# tuch-tara3.net
KiCad netlist of a schematic drawn in Altium Designer
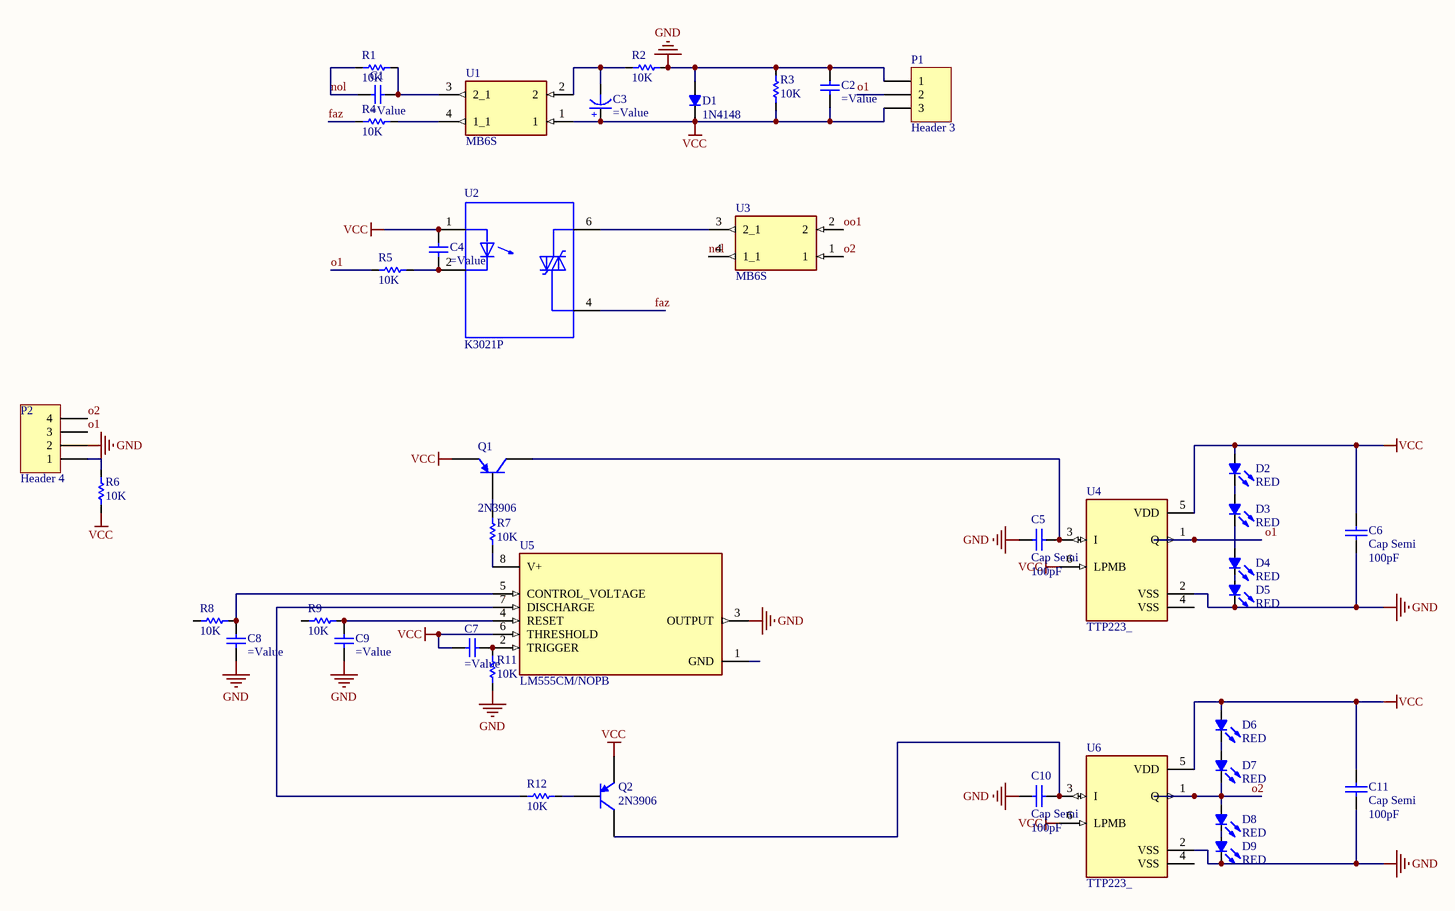
[diagram p0: tuch-tara3.SchDoc]

(export (version "E")
  (design (tool "Eeschema 10.0.6"))
  (components
    (comp (ref "C1")
      (value "~")
      (footprint "CAP-30")
      (description "Capacitor")
      (libsource (lib "AltiumLib1") (part "Capacitor"))
    )
    (comp (ref "C2")
      (value "~")
      (footprint "CAP 1206")
      (description "Capacitor")
      (libsource (lib "AltiumLib1") (part "Capacitor"))
    )
    (comp (ref "C3")
      (value "~")
      (footprint "ELEC-CAP-RAD10-20")
      (description "Electrolytic Capacitor")
      (libsource (lib "AltiumLib1") (part "Capacitor Electrolytic"))
    )
    (comp (ref "C4")
      (value "~")
      (footprint "CAP 1206")
      (description "Capacitor")
      (libsource (lib "AltiumLib1") (part "Capacitor"))
    )
    (comp (ref "C5")
      (value "Cap Semi")
      (footprint "AltiumLib1:CAP 0805")
      (description "Capacitor (Semiconductor SIM Model)")
      (fields (field (name "ALTIUM_VALUE") "100pF") (field (name "PUBLISHER") "Altium Limited"))
      (libsource (lib "Miscellaneous Devices") (part "Cap Semi"))
    )
    (comp (ref "C6")
      (value "Cap Semi")
      (footprint "C1206")
      (description "Capacitor (Semiconductor SIM Model)")
      (fields (field (name "ALTIUM_VALUE") "100pF") (field (name "PUBLISHER") "Altium Limited"))
      (libsource (lib "Miscellaneous Devices") (part "Cap Semi"))
    )
    (comp (ref "C7")
      (value "~")
      (footprint "CAP 0805")
      (description "Capacitor")
      (libsource (lib "AltiumLib1") (part "Capacitor"))
    )
    (comp (ref "C8")
      (value "~")
      (footprint "CAP 0805")
      (description "Capacitor")
      (libsource (lib "AltiumLib1") (part "Capacitor"))
    )
    (comp (ref "C9")
      (value "~")
      (footprint "CAP 0805")
      (description "Capacitor")
      (libsource (lib "AltiumLib1") (part "Capacitor"))
    )
    (comp (ref "C10")
      (value "Cap Semi")
      (footprint "AltiumLib1:CAP 0805")
      (description "Capacitor (Semiconductor SIM Model)")
      (fields (field (name "ALTIUM_VALUE") "100pF") (field (name "PUBLISHER") "Altium Limited"))
      (libsource (lib "Miscellaneous Devices") (part "Cap Semi"))
    )
    (comp (ref "C11")
      (value "Cap Semi")
      (footprint "C1206")
      (description "Capacitor (Semiconductor SIM Model)")
      (fields (field (name "ALTIUM_VALUE") "100pF") (field (name "PUBLISHER") "Altium Limited"))
      (libsource (lib "Miscellaneous Devices") (part "Cap Semi"))
    )
    (comp (ref "D1")
      (value "MODEL")
      (footprint "DO-41")
      (description "Diode")
      (fields (field (name "MODEL") "1N4148"))
      (libsource (lib "AltiumLib1") (part "Diode"))
    )
    (comp (ref "D2")
      (value "MODEL")
      (footprint "RES 1206 (3216X08L)")
      (description "Typical LED")
      (fields (field (name "COLOR") "RED"))
      (libsource (lib "AltiumLib1") (part "LED 5mm"))
    )
    (comp (ref "D3")
      (value "MODEL")
      (footprint "RES 1206 (3216X08L)")
      (description "Typical LED")
      (fields (field (name "COLOR") "RED"))
      (libsource (lib "AltiumLib1") (part "LED 5mm"))
    )
    (comp (ref "D4")
      (value "MODEL")
      (footprint "RES 1206 (3216X08L)")
      (description "Typical LED")
      (fields (field (name "COLOR") "RED"))
      (libsource (lib "AltiumLib1") (part "LED 5mm"))
    )
    (comp (ref "D5")
      (value "MODEL")
      (footprint "RES 1206 (3216X08L)")
      (description "Typical LED")
      (fields (field (name "COLOR") "RED"))
      (libsource (lib "AltiumLib1") (part "LED 5mm"))
    )
    (comp (ref "D6")
      (value "MODEL")
      (footprint "RES 1206 (3216X08L)")
      (description "Typical LED")
      (fields (field (name "COLOR") "RED"))
      (libsource (lib "AltiumLib1") (part "LED 5mm"))
    )
    (comp (ref "D7")
      (value "MODEL")
      (footprint "RES 1206 (3216X08L)")
      (description "Typical LED")
      (fields (field (name "COLOR") "RED"))
      (libsource (lib "AltiumLib1") (part "LED 5mm"))
    )
    (comp (ref "D8")
      (value "MODEL")
      (footprint "RES 1206 (3216X08L)")
      (description "Typical LED")
      (fields (field (name "COLOR") "RED"))
      (libsource (lib "AltiumLib1") (part "LED 5mm"))
    )
    (comp (ref "D9")
      (value "MODEL")
      (footprint "RES 1206 (3216X08L)")
      (description "Typical LED")
      (fields (field (name "COLOR") "RED"))
      (libsource (lib "AltiumLib1") (part "LED 5mm"))
    )
    (comp (ref "P1")
      (value "Header 3")
      (footprint "HDR1X3")
      (description "Header, 3-Pin")
      (fields (field (name "PUBLISHER") "Altium Limited"))
      (libsource (lib "Miscellaneous Connectors") (part "Header 3"))
    )
    (comp (ref "P2")
      (value "Header 4")
      (footprint "HDR1X4")
      (description "Header, 4-Pin")
      (fields (field (name "PUBLISHER") "Altium Limited"))
      (libsource (lib "Miscellaneous Connectors") (part "Header 4"))
    )
    (comp (ref "Q1")
      (value "2N3906")
      (footprint "MMBT3904-TP:SOT23-3")
      (description "PNP General Purpose Amplifier")
      (fields (field (name "PUBLISHER") "Altium Limited"))
      (libsource (lib "Miscellaneous Devices") (part "2N3906"))
    )
    (comp (ref "Q2")
      (value "2N3906")
      (footprint "MMBT3904-TP:SOT23-3")
      (description "PNP General Purpose Amplifier")
      (fields (field (name "PUBLISHER") "Altium Limited"))
      (libsource (lib "Miscellaneous Devices") (part "2N3906"))
    )
    (comp (ref "R1")
      (value "10K")
      (footprint "RES 1206 (3216X08L)")
      (description "Resistor")
      (fields (field (name "TOLERANCE") "5%") (field (name "POWER") "1/4 W"))
      (libsource (lib "AltiumLib1") (part "Resistor"))
    )
    (comp (ref "R2")
      (value "10K")
      (footprint "RES 1206 (3216X08L)")
      (description "Resistor")
      (fields (field (name "TOLERANCE") "5%") (field (name "POWER") "1/4 W"))
      (libsource (lib "AltiumLib1") (part "Resistor"))
    )
    (comp (ref "R3")
      (value "10K")
      (footprint "RES 1206 (3216X08L)")
      (description "Resistor")
      (fields (field (name "TOLERANCE") "5%") (field (name "POWER") "1/4 W"))
      (libsource (lib "AltiumLib1") (part "Resistor"))
    )
    (comp (ref "R4")
      (value "10K")
      (footprint "Res-(1/1)")
      (description "Resistor")
      (fields (field (name "TOLERANCE") "5%") (field (name "POWER") "1/4 W"))
      (libsource (lib "AltiumLib1") (part "Resistor"))
    )
    (comp (ref "R5")
      (value "10K")
      (footprint "RES 1206 (3216X08L)")
      (description "Resistor")
      (fields (field (name "TOLERANCE") "5%") (field (name "POWER") "1/4 W"))
      (libsource (lib "AltiumLib1") (part "Resistor"))
    )
    (comp (ref "R6")
      (value "10K")
      (footprint "Res-(1/4)")
      (description "Resistor")
      (fields (field (name "TOLERANCE") "5%") (field (name "POWER") "1/4 W"))
      (libsource (lib "AltiumLib1") (part "Resistor"))
    )
    (comp (ref "R7")
      (value "10K")
      (footprint "RES 1206 (3216X08L)")
      (description "Resistor")
      (fields (field (name "TOLERANCE") "5%") (field (name "POWER") "1/4 W"))
      (libsource (lib "AltiumLib1") (part "Resistor"))
    )
    (comp (ref "R8")
      (value "10K")
      (footprint "RES 0805 (2012X06L)")
      (description "Resistor")
      (fields (field (name "TOLERANCE") "5%") (field (name "POWER") "1/4 W"))
      (libsource (lib "AltiumLib1") (part "Resistor"))
    )
    (comp (ref "R9")
      (value "10K")
      (footprint "RES 0805 (2012X06L)")
      (description "Resistor")
      (fields (field (name "TOLERANCE") "5%") (field (name "POWER") "1/4 W"))
      (libsource (lib "AltiumLib1") (part "Resistor"))
    )
    (comp (ref "R11")
      (value "10K")
      (footprint "RES 0805 (2012X06L)")
      (description "Resistor")
      (fields (field (name "TOLERANCE") "5%") (field (name "POWER") "1/4 W"))
      (libsource (lib "AltiumLib1") (part "Resistor"))
    )
    (comp (ref "R12")
      (value "10K")
      (footprint "RES 0805 (2012X06L)")
      (description "Resistor")
      (fields (field (name "TOLERANCE") "5%") (field (name "POWER") "1/4 W"))
      (libsource (lib "AltiumLib1") (part "Resistor"))
    )
    (comp (ref "U1")
      (value "MB6S")
      (footprint "SOIC245P670X270-4N")
      (description "Bridge Rectifier Single Phase Standard 600V Surface Mount 4-SOIC")
      (fields (field (name "MF") "ON Semiconductor") (field (name "DIGI-KEY_PART_NUMBER") "MB6SCT-ND"))
      (libsource (lib "MB6S") (part "MB6S"))
    )
    (comp (ref "U2")
      (value "K3021P")
      (footprint "DIP762W50P254L730H410Q6")
      (description "Optoisolator Triac Output 5300Vrms 1 Channel 6-DIP")
      (fields (field (name "MF") "Vishay Semiconductor"))
      (libsource (lib "K3021P") (part "K3021P"))
    )
    (comp (ref "U3")
      (value "MB6S")
      (footprint "SOIC245P670X270-4N")
      (description "Bridge Rectifier Single Phase Standard 600V Surface Mount 4-SOIC")
      (fields (field (name "MF") "ON Semiconductor") (field (name "DIGI-KEY_PART_NUMBER") "MB6SCT-ND"))
      (libsource (lib "MB6S") (part "MB6S"))
    )
    (comp (ref "U4")
      (value "TTP223_")
      (footprint "SOT95P285X126-6N")
      (fields (field (name "MP") "TTP223") (field (name "MF") "KOA Speer"))
      (libsource (lib "TTP223_") (part "TTP223_"))
    )
    (comp (ref "U5")
      (value "LM555CM/NOPB")
      (footprint "SOIC127P599X175-8N")
      (description "Highly Stable 555 Timer 8-SOIC 0 to 70")
      (libsource (lib "LM555CM_NOPB") (part "LM555CM/NOPB"))
    )
    (comp (ref "U6")
      (value "TTP223_")
      (footprint "SOT95P285X126-6N")
      (fields (field (name "MP") "TTP223") (field (name "MF") "KOA Speer"))
      (libsource (lib "TTP223_") (part "TTP223_"))
    )
  )
  (nets
    (net (code "1") (name "/faz") (class "Default")
      (node (ref "R4") (pin "2") (pinfunction "2_2") (pintype "passive"))
      (node (ref "U2") (pin "4") (pinfunction "MT1_4") (pintype "passive"))
    )
    (net (code "2") (name "/nol") (class "Default")
      (node (ref "C1") (pin "1") (pinfunction "+_1") (pintype "passive"))
      (node (ref "R1") (pin "2") (pinfunction "2_2") (pintype "passive"))
      (node (ref "U3") (pin "4") (pinfunction "1_1_4") (pintype "output"))
    )
    (net (code "3") (name "/o1") (class "Default")
      (node (ref "P1") (pin "2") (pinfunction "2_2") (pintype "passive"))
      (node (ref "P2") (pin "3") (pinfunction "3_3") (pintype "passive"))
      (node (ref "R5") (pin "1") (pinfunction "1_1") (pintype "passive"))
    )
    (net (code "4") (name "/o2") (class "Default")
      (node (ref "D7") (pin "2") (pinfunction "K_2") (pintype "passive"))
      (node (ref "D8") (pin "1") (pinfunction "A_1") (pintype "passive"))
      (node (ref "P2") (pin "4") (pinfunction "4_4") (pintype "passive"))
      (node (ref "U3") (pin "1") (pinfunction "1_1") (pintype "input"))
      (node (ref "U6") (pin "1") (pinfunction "Q_1") (pintype "output"))
    )
    (net (code "5") (name "/oo1") (class "Default")
      (node (ref "U3") (pin "2") (pinfunction "2_2") (pintype "input"))
    )
    (net (code "6") (name "GND") (class "Default")
      (node (ref "C10") (pin "2") (pinfunction "2_2") (pintype "passive"))
      (node (ref "C11") (pin "1") (pinfunction "1_1") (pintype "passive"))
      (node (ref "C2") (pin "2") (pinfunction "-_2") (pintype "passive"))
      (node (ref "C5") (pin "2") (pinfunction "2_2") (pintype "passive"))
      (node (ref "C6") (pin "1") (pinfunction "1_1") (pintype "passive"))
      (node (ref "C8") (pin "2") (pinfunction "-_2") (pintype "passive"))
      (node (ref "C9") (pin "2") (pinfunction "-_2") (pintype "passive"))
      (node (ref "D1") (pin "1") (pinfunction "A_1") (pintype "passive"))
      (node (ref "D5") (pin "2") (pinfunction "K_2") (pintype "passive"))
      (node (ref "D9") (pin "2") (pinfunction "K_2") (pintype "passive"))
      (node (ref "P1") (pin "1") (pinfunction "1_1") (pintype "passive"))
      (node (ref "P2") (pin "2") (pinfunction "2_2") (pintype "passive"))
      (node (ref "R11") (pin "1") (pinfunction "1_1") (pintype "passive"))
      (node (ref "R2") (pin "2") (pinfunction "2_2") (pintype "passive"))
      (node (ref "R3") (pin "2") (pinfunction "2_2") (pintype "passive"))
      (node (ref "U4") (pin "2") (pinfunction "VSS_2") (pintype "power_in"))
      (node (ref "U5") (pin "3") (pinfunction "OUTPUT_3") (pintype "output"))
      (node (ref "U6") (pin "2") (pinfunction "VSS_2") (pintype "power_in"))
    )
    (net (code "7") (name "Net-(C1--)") (class "Default")
      (node (ref "C1") (pin "2") (pinfunction "-_2") (pintype "passive"))
      (node (ref "R1") (pin "1") (pinfunction "1_1") (pintype "passive"))
      (node (ref "U1") (pin "3") (pinfunction "2_1_3") (pintype "output"))
    )
    (net (code "8") (name "Net-(C3--)") (class "Default")
      (node (ref "C3") (pin "1") (pinfunction "-_1") (pintype "passive"))
      (node (ref "R2") (pin "1") (pinfunction "1_1") (pintype "passive"))
      (node (ref "U1") (pin "2") (pinfunction "2_2") (pintype "input"))
    )
    (net (code "9") (name "Net-(C4-+)") (class "Default")
      (node (ref "C4") (pin "1") (pinfunction "+_1") (pintype "passive"))
      (node (ref "R5") (pin "2") (pinfunction "2_2") (pintype "passive"))
      (node (ref "U2") (pin "2") (pinfunction "C_2") (pintype "passive"))
    )
    (net (code "10") (name "Net-(C7-+)") (class "Default")
      (node (ref "C7") (pin "1") (pinfunction "+_1") (pintype "passive"))
      (node (ref "R11") (pin "2") (pinfunction "2_2") (pintype "passive"))
      (node (ref "U5") (pin "2") (pinfunction "TRIGGER_2") (pintype "input"))
    )
    (net (code "11") (name "Net-(C8-+)") (class "Default")
      (node (ref "C8") (pin "1") (pinfunction "+_1") (pintype "passive"))
      (node (ref "R8") (pin "2") (pinfunction "2_2") (pintype "passive"))
      (node (ref "U5") (pin "5") (pinfunction "CONTROL_VOLTAGE_5") (pintype "input"))
    )
    (net (code "12") (name "Net-(C9-+)") (class "Default")
      (node (ref "C9") (pin "1") (pinfunction "+_1") (pintype "passive"))
      (node (ref "R9") (pin "2") (pinfunction "2_2") (pintype "passive"))
      (node (ref "U5") (pin "4") (pinfunction "RESET_4") (pintype "input"))
    )
    (net (code "13") (name "Net-(D2-K)") (class "Default")
      (node (ref "D2") (pin "2") (pinfunction "K_2") (pintype "passive"))
      (node (ref "D3") (pin "1") (pinfunction "A_1") (pintype "passive"))
    )
    (net (code "14") (name "Net-(D3-K)") (class "Default")
      (node (ref "D3") (pin "2") (pinfunction "K_2") (pintype "passive"))
      (node (ref "D4") (pin "1") (pinfunction "A_1") (pintype "passive"))
    )
    (net (code "15") (name "Net-(D4-K)") (class "Default")
      (node (ref "D4") (pin "2") (pinfunction "K_2") (pintype "passive"))
      (node (ref "D5") (pin "1") (pinfunction "A_1") (pintype "passive"))
    )
    (net (code "16") (name "Net-(D6-K)") (class "Default")
      (node (ref "D6") (pin "2") (pinfunction "K_2") (pintype "passive"))
      (node (ref "D7") (pin "1") (pinfunction "A_1") (pintype "passive"))
    )
    (net (code "17") (name "Net-(D8-K)") (class "Default")
      (node (ref "D8") (pin "2") (pinfunction "K_2") (pintype "passive"))
      (node (ref "D9") (pin "1") (pinfunction "A_1") (pintype "passive"))
    )
    (net (code "18") (name "Net-(P2-Pad1)") (class "Default")
      (node (ref "P2") (pin "1") (pinfunction "1_1") (pintype "passive"))
      (node (ref "R6") (pin "2") (pinfunction "2_2") (pintype "passive"))
    )
    (net (code "19") (name "Net-(Q1-B)") (class "Default")
      (node (ref "Q1") (pin "2") (pinfunction "B_2") (pintype "passive"))
      (node (ref "R7") (pin "2") (pinfunction "2_2") (pintype "passive"))
    )
    (net (code "20") (name "Net-(Q1-C)") (class "Default")
      (node (ref "C5") (pin "1") (pinfunction "1_1") (pintype "passive"))
      (node (ref "Q1") (pin "3") (pinfunction "C_3") (pintype "passive"))
      (node (ref "U4") (pin "3") (pinfunction "I_3") (pintype "bidirectional"))
    )
    (net (code "21") (name "Net-(Q2-B)") (class "Default")
      (node (ref "Q2") (pin "2") (pinfunction "B_2") (pintype "passive"))
      (node (ref "R12") (pin "2") (pinfunction "2_2") (pintype "passive"))
    )
    (net (code "22") (name "Net-(Q2-C)") (class "Default")
      (node (ref "C10") (pin "1") (pinfunction "1_1") (pintype "passive"))
      (node (ref "Q2") (pin "3") (pinfunction "C_3") (pintype "passive"))
      (node (ref "U6") (pin "3") (pinfunction "I_3") (pintype "bidirectional"))
    )
    (net (code "23") (name "Net-(U1-1_1)") (class "Default")
      (node (ref "R4") (pin "1") (pinfunction "1_1") (pintype "passive"))
      (node (ref "U1") (pin "4") (pinfunction "1_1_4") (pintype "output"))
    )
    (net (code "24") (name "Net-(U2-MT2)") (class "Default")
      (node (ref "U2") (pin "6") (pinfunction "MT2_6") (pintype "passive"))
      (node (ref "U3") (pin "3") (pinfunction "2_1_3") (pintype "output"))
    )
    (net (code "25") (name "Net-(U5-DISCHARGE)") (class "Default")
      (node (ref "R12") (pin "1") (pinfunction "1_1") (pintype "passive"))
      (node (ref "U5") (pin "7") (pinfunction "DISCHARGE_7") (pintype "input"))
    )
    (net (code "26") (name "Net-(U5-V+)") (class "Default")
      (node (ref "R7") (pin "1") (pinfunction "1_1") (pintype "passive"))
      (node (ref "U5") (pin "8") (pinfunction "V+_8") (pintype "power_in"))
    )
    (net (code "27") (name "VCC") (class "Default")
      (node (ref "C11") (pin "2") (pinfunction "2_2") (pintype "passive"))
      (node (ref "C2") (pin "1") (pinfunction "+_1") (pintype "passive"))
      (node (ref "C3") (pin "2") (pinfunction "+_2") (pintype "passive"))
      (node (ref "C4") (pin "2") (pinfunction "-_2") (pintype "passive"))
      (node (ref "C6") (pin "2") (pinfunction "2_2") (pintype "passive"))
      (node (ref "C7") (pin "2") (pinfunction "-_2") (pintype "passive"))
      (node (ref "D1") (pin "2") (pinfunction "K_2") (pintype "passive"))
      (node (ref "D2") (pin "1") (pinfunction "A_1") (pintype "passive"))
      (node (ref "D6") (pin "1") (pinfunction "A_1") (pintype "passive"))
      (node (ref "P1") (pin "3") (pinfunction "3_3") (pintype "passive"))
      (node (ref "Q1") (pin "1") (pinfunction "E_1") (pintype "passive"))
      (node (ref "Q2") (pin "1") (pinfunction "E_1") (pintype "passive"))
      (node (ref "R3") (pin "1") (pinfunction "1_1") (pintype "passive"))
      (node (ref "R6") (pin "1") (pinfunction "1_1") (pintype "passive"))
      (node (ref "U1") (pin "1") (pinfunction "1_1") (pintype "input"))
      (node (ref "U2") (pin "1") (pinfunction "A_1") (pintype "passive"))
      (node (ref "U4") (pin "5") (pinfunction "VDD_5") (pintype "power_in"))
      (node (ref "U4") (pin "6") (pinfunction "LPMB_6") (pintype "input"))
      (node (ref "U5") (pin "6") (pinfunction "THRESHOLD_6") (pintype "input"))
      (node (ref "U6") (pin "5") (pinfunction "VDD_5") (pintype "power_in"))
      (node (ref "U6") (pin "6") (pinfunction "LPMB_6") (pintype "input"))
    )
    (net (code "28") (name "unconnected-(R8-Pad1)") (class "Default")
      (node (ref "R8") (pin "1") (pinfunction "1_1") (pintype "passive"))
    )
    (net (code "29") (name "unconnected-(R9-Pad1)") (class "Default")
      (node (ref "R9") (pin "1") (pinfunction "1_1") (pintype "passive"))
    )
    (net (code "30") (name "unconnected-(U4-Q-Pad1)") (class "Default")
      (node (ref "U4") (pin "1") (pinfunction "Q_1") (pintype "output"))
    )
    (net (code "31") (name "unconnected-(U4-VSS-Pad4)") (class "Default")
      (node (ref "U4") (pin "4") (pinfunction "VSS_4") (pintype "power_in"))
    )
    (net (code "32") (name "unconnected-(U5-GND-Pad1)") (class "Default")
      (node (ref "U5") (pin "1") (pinfunction "GND_1") (pintype "power_in"))
    )
    (net (code "33") (name "unconnected-(U6-VSS-Pad4)") (class "Default")
      (node (ref "U6") (pin "4") (pinfunction "VSS_4") (pintype "power_in"))
    )
  )
)
